# buck2.net
KiCad netlist of a schematic drawn in Altium Designer
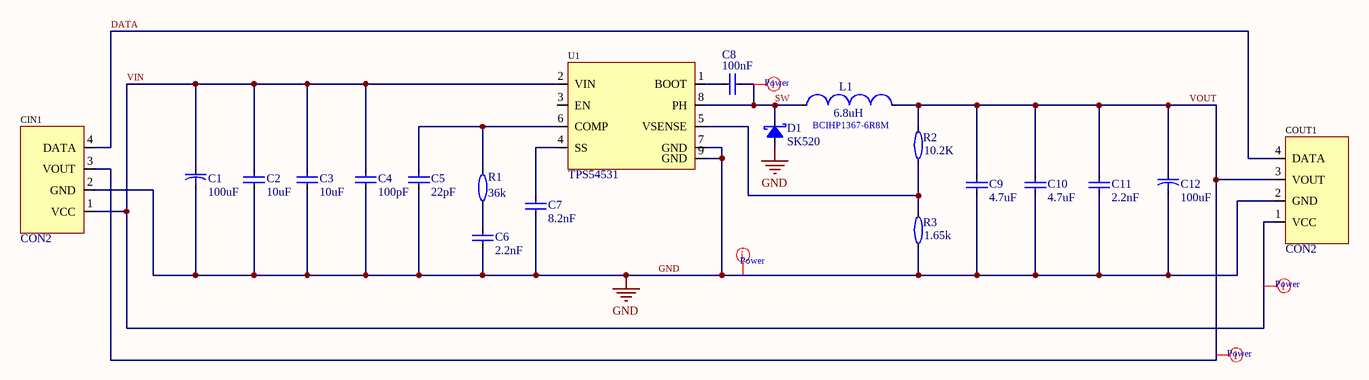
[diagram p0: buck2.SchDoc]

(export (version "E")
  (design (tool "Eeschema 10.0.6"))
  (components
    (comp (ref "C1")
      (value "100uF")
      (footprint "CAPAE10083X104N")
      (description "Capacitor")
      (fields (field (name "Comment") "Cap2") (field (name "PUBLISHER") "Altium Limited"))
      (libsource (lib "buck2") (part "Cap2"))
    )
    (comp (ref "C2")
      (value "10uF")
      (footprint "CAPC_1206_3216X16L")
      (description "Capacitor")
      (fields (field (name "Comment") "Cap") (field (name "PUBLISHER") "Altium Limited"))
      (libsource (lib "buck2") (part "Cap"))
    )
    (comp (ref "C3")
      (value "10uF")
      (footprint "CAPC_1206_3216X16L")
      (description "Capacitor")
      (fields (field (name "Comment") "Cap") (field (name "PUBLISHER") "Altium Limited"))
      (libsource (lib "buck2") (part "Cap"))
    )
    (comp (ref "C4")
      (value "100pF")
      (footprint "CAPC_0603_1608X08L")
      (description "Capacitor")
      (fields (field (name "Comment") "Cap") (field (name "PUBLISHER") "Altium Limited"))
      (libsource (lib "buck2") (part "Cap"))
    )
    (comp (ref "C5")
      (value "22pF")
      (footprint "CAPC_0603_1608X08L")
      (description "Capacitor")
      (fields (field (name "Comment") "Cap") (field (name "PUBLISHER") "Altium Limited"))
      (libsource (lib "buck2") (part "Cap"))
    )
    (comp (ref "C6")
      (value "2.2nF")
      (footprint "CAPC_0603_1608X08L")
      (description "Capacitor")
      (fields (field (name "Comment") "Cap") (field (name "PUBLISHER") "Altium Limited"))
      (libsource (lib "buck2") (part "Cap"))
    )
    (comp (ref "C7")
      (value "8.2nF")
      (footprint "CAPC_0603_1608X08L")
      (description "Capacitor")
      (fields (field (name "Comment") "Cap") (field (name "PUBLISHER") "Altium Limited"))
      (libsource (lib "buck2") (part "Cap"))
    )
    (comp (ref "C8")
      (value "100nF")
      (footprint "CAPC_0603_1608X08L")
      (description "Capacitor")
      (fields (field (name "Comment") "Cap") (field (name "PUBLISHER") "Altium Limited"))
      (libsource (lib "buck2") (part "Cap"))
    )
    (comp (ref "C9")
      (value "4.7uF")
      (footprint "CAPC_1206_3216X16L")
      (description "Capacitor")
      (fields (field (name "Comment") "Cap") (field (name "PUBLISHER") "Altium Limited"))
      (libsource (lib "buck2") (part "Cap"))
    )
    (comp (ref "C10")
      (value "4.7uF")
      (footprint "CAPC_1206_3216X16L")
      (description "Capacitor")
      (fields (field (name "Comment") "Cap") (field (name "PUBLISHER") "Altium Limited"))
      (libsource (lib "buck2") (part "Cap"))
    )
    (comp (ref "C11")
      (value "2.2nF")
      (footprint "CAPC_0603_1608X08L")
      (description "Capacitor")
      (fields (field (name "Comment") "Cap") (field (name "PUBLISHER") "Altium Limited"))
      (libsource (lib "buck2") (part "Cap"))
    )
    (comp (ref "C12")
      (value "100uF")
      (footprint "CAPAE10083X104N")
      (description "Capacitor")
      (fields (field (name "Comment") "Cap2") (field (name "PUBLISHER") "Altium Limited"))
      (libsource (lib "buck2") (part "Cap2"))
    )
    (comp (ref "CIN1") (value "CON2") (footprint "CONNECTOR") (libsource (lib "buck2") (part "CON2")))
    (comp (ref "COUT1") (value "CON2") (footprint "CONNECTOR") (libsource (lib "") (part "CON2_1")))
    (comp (ref "D1")
      (value "SK520")
      (footprint "CDBC-G")
      (description "Schottky Diode")
      (fields (field (name "PUBLISHER") "Altium Limited"))
      (libsource (lib "buck2") (part "D Schottky"))
    )
    (comp (ref "L1")
      (value "6.8uH")
      (footprint "INDP130128X70N")
      (description "Inductor")
      (fields (field (name "PART") "BCIHP1367-6R8M") (field (name "PUBLISHER") "Altium Limited"))
      (libsource (lib "buck2") (part "Inductor"))
    )
    (comp (ref "R1")
      (value "36k")
      (footprint "RESC_0603_1608X08L")
      (description "Resistor")
      (fields (field (name "Comment") "Res2") (field (name "PUBLISHER") "Altium Limited"))
      (libsource (lib "buck2") (part "Res2"))
    )
    (comp (ref "R2")
      (value "10.2K")
      (footprint "RESC_0603_1608X08L")
      (description "Resistor")
      (fields (field (name "Comment") "Res2") (field (name "PUBLISHER") "Altium Limited"))
      (libsource (lib "buck2") (part "Res2"))
    )
    (comp (ref "R3")
      (value "1.65k")
      (footprint "RESC_0603_1608X08L")
      (description "Resistor")
      (fields (field (name "Comment") "Res2") (field (name "PUBLISHER") "Altium Limited"))
      (libsource (lib "buck2") (part "Res2"))
    )
    (comp (ref "U1")
      (value "TPS54531")
      (footprint "SOIC127P600X150_HS-9L")
      (libsource (lib "buck2") (part "TPS54531"))
    )
  )
  (nets
    (net (code "1") (name "/DATA") (class "Default")
      (node (ref "CIN1") (pin "4") (pinfunction "DATA_4") (pintype "passive"))
      (node (ref "COUT1") (pin "4") (pinfunction "DATA_4") (pintype "passive"))
    )
    (net (code "2") (name "/SW") (class "Default")
      (node (ref "C8") (pin "1") (pinfunction "1_1") (pintype "passive"))
      (node (ref "D1") (pin "2") (pinfunction "K_2") (pintype "passive"))
      (node (ref "L1") (pin "1") (pinfunction "1_1") (pintype "passive"))
      (node (ref "U1") (pin "8") (pinfunction "PH_8") (pintype "passive"))
    )
    (net (code "3") (name "/VIN") (class "Default")
      (node (ref "C1") (pin "1") (pinfunction "1_1") (pintype "passive"))
      (node (ref "C2") (pin "2") (pinfunction "2_2") (pintype "passive"))
      (node (ref "C3") (pin "2") (pinfunction "2_2") (pintype "passive"))
      (node (ref "C4") (pin "2") (pinfunction "2_2") (pintype "passive"))
      (node (ref "CIN1") (pin "1") (pinfunction "VCC_1") (pintype "passive"))
      (node (ref "COUT1") (pin "1") (pinfunction "VCC_1") (pintype "passive"))
      (node (ref "U1") (pin "2") (pinfunction "VIN_2") (pintype "passive"))
    )
    (net (code "4") (name "/VOUT") (class "Default")
      (node (ref "C10") (pin "1") (pinfunction "1_1") (pintype "passive"))
      (node (ref "C11") (pin "1") (pinfunction "1_1") (pintype "passive"))
      (node (ref "C12") (pin "1") (pinfunction "1_1") (pintype "passive"))
      (node (ref "C9") (pin "1") (pinfunction "1_1") (pintype "passive"))
      (node (ref "CIN1") (pin "3") (pinfunction "VOUT_3") (pintype "passive"))
      (node (ref "COUT1") (pin "3") (pinfunction "VOUT_3") (pintype "passive"))
      (node (ref "L1") (pin "2") (pinfunction "2_2") (pintype "passive"))
      (node (ref "R2") (pin "2") (pinfunction "2_2") (pintype "passive"))
    )
    (net (code "5") (name "GND") (class "Default")
      (node (ref "C1") (pin "2") (pinfunction "2_2") (pintype "passive"))
      (node (ref "C10") (pin "2") (pinfunction "2_2") (pintype "passive"))
      (node (ref "C11") (pin "2") (pinfunction "2_2") (pintype "passive"))
      (node (ref "C12") (pin "2") (pinfunction "2_2") (pintype "passive"))
      (node (ref "C2") (pin "1") (pinfunction "1_1") (pintype "passive"))
      (node (ref "C3") (pin "1") (pinfunction "1_1") (pintype "passive"))
      (node (ref "C4") (pin "1") (pinfunction "1_1") (pintype "passive"))
      (node (ref "C5") (pin "1") (pinfunction "1_1") (pintype "passive"))
      (node (ref "C6") (pin "1") (pinfunction "1_1") (pintype "passive"))
      (node (ref "C7") (pin "1") (pinfunction "1_1") (pintype "passive"))
      (node (ref "C9") (pin "2") (pinfunction "2_2") (pintype "passive"))
      (node (ref "CIN1") (pin "2") (pinfunction "GND_2") (pintype "passive"))
      (node (ref "COUT1") (pin "2") (pinfunction "GND_2") (pintype "passive"))
      (node (ref "D1") (pin "1") (pinfunction "A_1") (pintype "passive"))
      (node (ref "R3") (pin "1") (pinfunction "1_1") (pintype "passive"))
      (node (ref "U1") (pin "7") (pinfunction "GND_7") (pintype "passive"))
      (node (ref "U1") (pin "9") (pinfunction "GND_9") (pintype "passive"))
    )
    (net (code "6") (name "Net-(C6-Pad2)") (class "Default")
      (node (ref "C6") (pin "2") (pinfunction "2_2") (pintype "passive"))
      (node (ref "R1") (pin "1") (pinfunction "1_1") (pintype "passive"))
    )
    (net (code "7") (name "Net-(U1-BOOT)") (class "Default")
      (node (ref "C8") (pin "2") (pinfunction "2_2") (pintype "passive"))
      (node (ref "U1") (pin "1") (pinfunction "BOOT_1") (pintype "passive"))
    )
    (net (code "8") (name "Net-(U1-COMP)") (class "Default")
      (node (ref "C5") (pin "2") (pinfunction "2_2") (pintype "passive"))
      (node (ref "R1") (pin "2") (pinfunction "2_2") (pintype "passive"))
      (node (ref "U1") (pin "6") (pinfunction "COMP_6") (pintype "passive"))
    )
    (net (code "9") (name "Net-(U1-SS)") (class "Default")
      (node (ref "C7") (pin "2") (pinfunction "2_2") (pintype "passive"))
      (node (ref "U1") (pin "4") (pinfunction "SS_4") (pintype "passive"))
    )
    (net (code "10") (name "Net-(U1-VSENSE)") (class "Default")
      (node (ref "R2") (pin "1") (pinfunction "1_1") (pintype "passive"))
      (node (ref "R3") (pin "2") (pinfunction "2_2") (pintype "passive"))
      (node (ref "U1") (pin "5") (pinfunction "VSENSE_5") (pintype "passive"))
    )
    (net (code "11") (name "unconnected-(U1-EN-Pad3)") (class "Default")
      (node (ref "U1") (pin "3") (pinfunction "EN_3") (pintype "passive"))
    )
  )
)
